# Block_GPIOs_USB2_0_I2S_SPI_GBe_and_CSI.net
KiCad netlist of a schematic drawn in Altium Designer
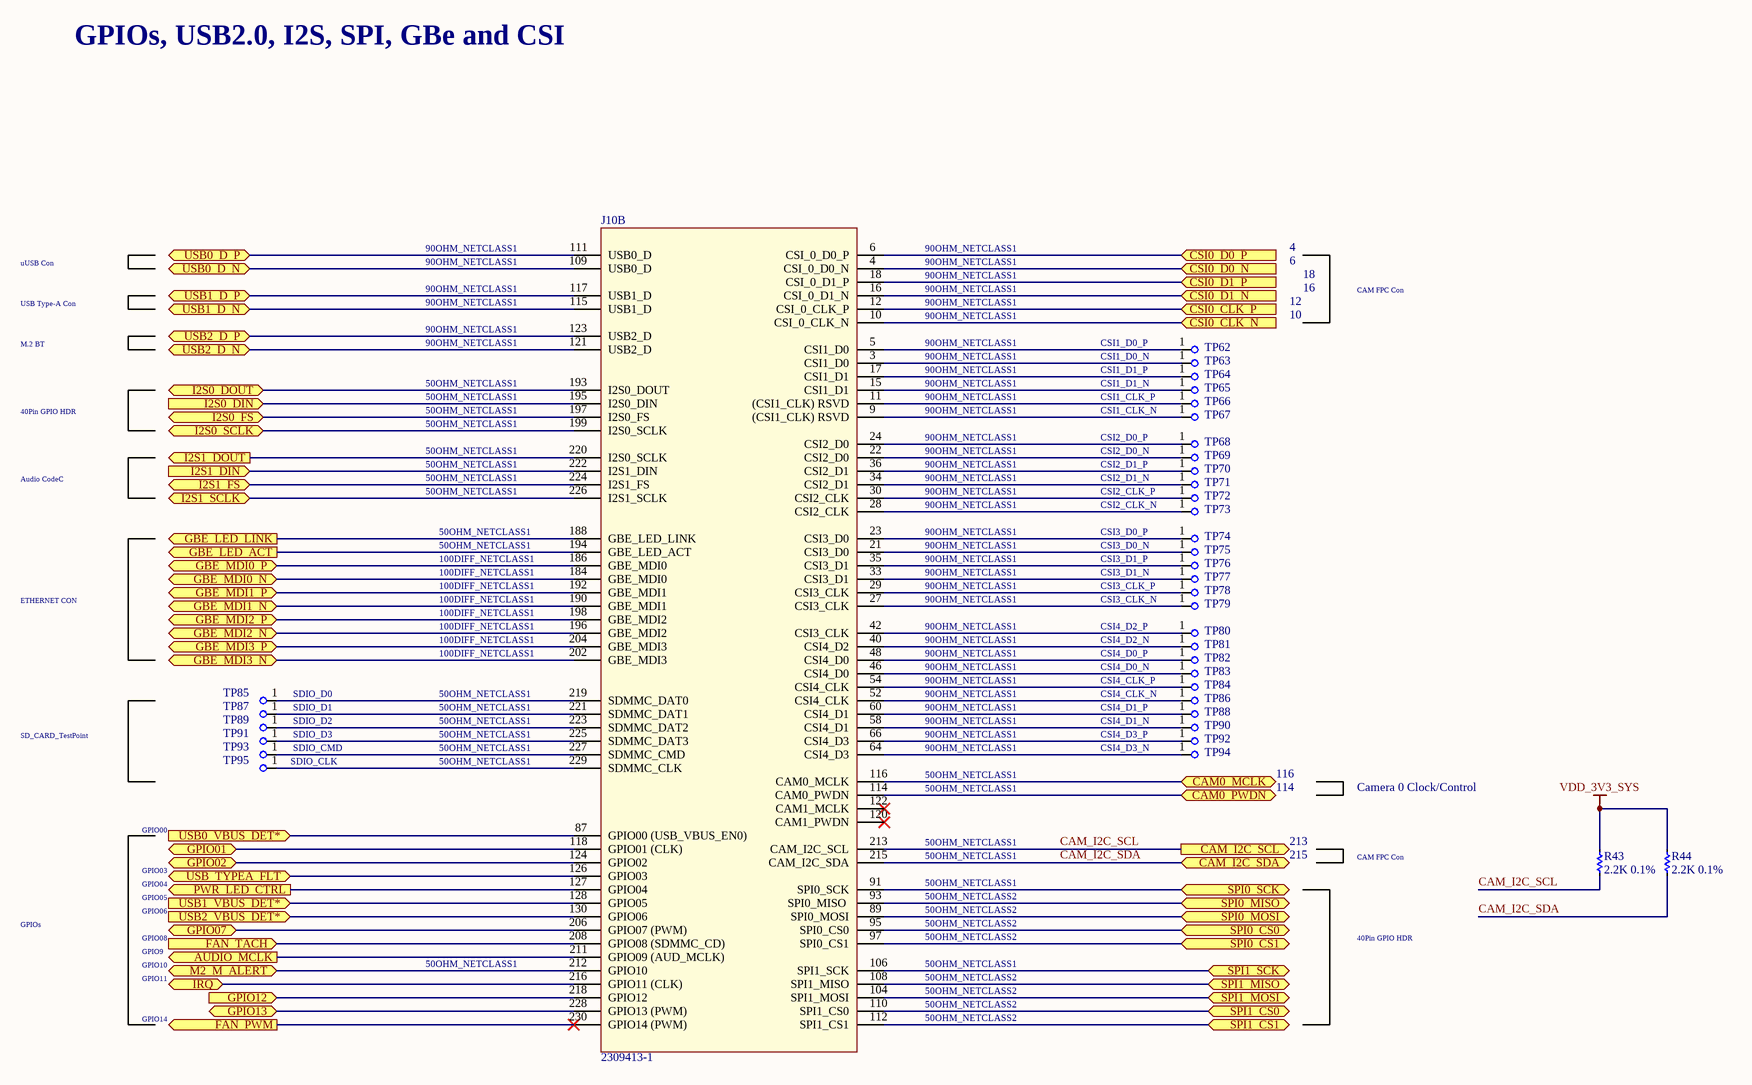
[diagram p0: Block_GPIOs, USB2.0, I2S, SPI, GBe and CSI.SchDoc]

(export (version "E")
  (design (tool "Eeschema 10.0.6"))
  (components
    (comp (ref "J10")
      (value "2309413-1")
      (footprint "2309413-1")
      (description "Conn DDR4 DIMM Socket SKT 260 POS 0.5mm Solder RA SMD T/R")
      (fields (field (name "MANUFACTURER") "TE Connectivity"))
      (libsource (lib "GM_Altium_Library") (part "2309413-1"))
    )
    (comp (ref "R43")
      (value "2.2K 0.1%")
      (footprint "R0603")
      (description "Res Thin Film 0603 2.2K Ohm 0.1% 1/16W ±25ppm/°C Molded SMD SMD Paper T/R")
      (fields
        (field (name "MANUFACTURER") "TE Connectivity Neohm")
        (field (name "MANUFACTURER PART NUMBER") "CPF0603B2K2E1")
      )
      (libsource (lib "GM_Altium_Library") (part "CPF0603B2K2E1"))
    )
    (comp (ref "R44")
      (value "2.2K 0.1%")
      (footprint "R0603")
      (description "Res Thin Film 0603 2.2K Ohm 0.1% 1/16W ±25ppm/°C Molded SMD SMD Paper T/R")
      (fields
        (field (name "MANUFACTURER") "TE Connectivity Neohm")
        (field (name "MANUFACTURER PART NUMBER") "CPF0603B2K2E1")
      )
      (libsource (lib "GM_Altium_Library") (part "CPF0603B2K2E1"))
    )
    (comp (ref "TP62")
      (value "CSI1_D0_P")
      (footprint "TestPoint_Pad_D1.0mm")
      (libsource (lib "GM_Altium_Library") (part "TestPoint_D1mm"))
    )
    (comp (ref "TP63")
      (value "CSI1_D0_N")
      (footprint "TestPoint_Pad_D1.0mm")
      (libsource (lib "GM_Altium_Library") (part "TestPoint_D1mm"))
    )
    (comp (ref "TP64")
      (value "CSI1_D1_P")
      (footprint "TestPoint_Pad_D1.0mm")
      (libsource (lib "GM_Altium_Library") (part "TestPoint_D1mm"))
    )
    (comp (ref "TP65")
      (value "CSI1_D1_N")
      (footprint "TestPoint_Pad_D1.0mm")
      (libsource (lib "GM_Altium_Library") (part "TestPoint_D1mm"))
    )
    (comp (ref "TP66")
      (value "CSI1_CLK_P")
      (footprint "TestPoint_Pad_D1.0mm")
      (libsource (lib "GM_Altium_Library") (part "TestPoint_D1mm"))
    )
    (comp (ref "TP67")
      (value "CSI1_CLK_N")
      (footprint "TestPoint_Pad_D1.0mm")
      (libsource (lib "GM_Altium_Library") (part "TestPoint_D1mm"))
    )
    (comp (ref "TP68")
      (value "CSI2_D0_P")
      (footprint "TestPoint_Pad_D1.0mm")
      (libsource (lib "GM_Altium_Library") (part "TestPoint_D1mm"))
    )
    (comp (ref "TP69")
      (value "CSI2_D0_N")
      (footprint "TestPoint_Pad_D1.0mm")
      (libsource (lib "GM_Altium_Library") (part "TestPoint_D1mm"))
    )
    (comp (ref "TP70")
      (value "CSI2_D1_P")
      (footprint "TestPoint_Pad_D1.0mm")
      (libsource (lib "GM_Altium_Library") (part "TestPoint_D1mm"))
    )
    (comp (ref "TP71")
      (value "CSI2_D1_N")
      (footprint "TestPoint_Pad_D1.0mm")
      (libsource (lib "GM_Altium_Library") (part "TestPoint_D1mm"))
    )
    (comp (ref "TP72")
      (value "CSI2_CLK_P")
      (footprint "TestPoint_Pad_D1.0mm")
      (libsource (lib "GM_Altium_Library") (part "TestPoint_D1mm"))
    )
    (comp (ref "TP73")
      (value "CSI2_CLK_N")
      (footprint "TestPoint_Pad_D1.0mm")
      (libsource (lib "GM_Altium_Library") (part "TestPoint_D1mm"))
    )
    (comp (ref "TP74")
      (value "CSI3_D0_P")
      (footprint "TestPoint_Pad_D1.0mm")
      (libsource (lib "GM_Altium_Library") (part "TestPoint_D1mm"))
    )
    (comp (ref "TP75")
      (value "CSI3_D0_N")
      (footprint "TestPoint_Pad_D1.0mm")
      (libsource (lib "GM_Altium_Library") (part "TestPoint_D1mm"))
    )
    (comp (ref "TP76")
      (value "CSI3_D1_P")
      (footprint "TestPoint_Pad_D1.0mm")
      (libsource (lib "GM_Altium_Library") (part "TestPoint_D1mm"))
    )
    (comp (ref "TP77")
      (value "CSI3_D1_N")
      (footprint "TestPoint_Pad_D1.0mm")
      (libsource (lib "GM_Altium_Library") (part "TestPoint_D1mm"))
    )
    (comp (ref "TP78")
      (value "CSI3_CLK_P")
      (footprint "TestPoint_Pad_D1.0mm")
      (libsource (lib "GM_Altium_Library") (part "TestPoint_D1mm"))
    )
    (comp (ref "TP79")
      (value "CSI3_CLK_N")
      (footprint "TestPoint_Pad_D1.0mm")
      (libsource (lib "GM_Altium_Library") (part "TestPoint_D1mm"))
    )
    (comp (ref "TP80")
      (value "CSI4_D2_P")
      (footprint "TestPoint_Pad_D1.0mm")
      (libsource (lib "GM_Altium_Library") (part "TestPoint_D1mm"))
    )
    (comp (ref "TP81")
      (value "CSI4_D2_N")
      (footprint "TestPoint_Pad_D1.0mm")
      (libsource (lib "GM_Altium_Library") (part "TestPoint_D1mm"))
    )
    (comp (ref "TP82")
      (value "CSI4_D0_P")
      (footprint "TestPoint_Pad_D1.0mm")
      (libsource (lib "GM_Altium_Library") (part "TestPoint_D1mm"))
    )
    (comp (ref "TP83")
      (value "CSI4_D0_N")
      (footprint "TestPoint_Pad_D1.0mm")
      (libsource (lib "GM_Altium_Library") (part "TestPoint_D1mm"))
    )
    (comp (ref "TP84")
      (value "CSI4_CLK_P")
      (footprint "TestPoint_Pad_D1.0mm")
      (libsource (lib "GM_Altium_Library") (part "TestPoint_D1mm"))
    )
    (comp (ref "TP85")
      (value "SDIO_D0")
      (footprint "TestPoint_Pad_D1.0mm")
      (libsource (lib "GM_Altium_Library") (part "TestPoint_D1mm"))
    )
    (comp (ref "TP86")
      (value "CSI4_CLK_N")
      (footprint "TestPoint_Pad_D1.0mm")
      (libsource (lib "GM_Altium_Library") (part "TestPoint_D1mm"))
    )
    (comp (ref "TP87")
      (value "SDIO_D1")
      (footprint "TestPoint_Pad_D1.0mm")
      (libsource (lib "GM_Altium_Library") (part "TestPoint_D1mm"))
    )
    (comp (ref "TP88")
      (value "CSI4_D1_P")
      (footprint "TestPoint_Pad_D1.0mm")
      (libsource (lib "GM_Altium_Library") (part "TestPoint_D1mm"))
    )
    (comp (ref "TP89")
      (value "SDIO_D2")
      (footprint "TestPoint_Pad_D1.0mm")
      (libsource (lib "GM_Altium_Library") (part "TestPoint_D1mm"))
    )
    (comp (ref "TP90")
      (value "CSI4_D1_N")
      (footprint "TestPoint_Pad_D1.0mm")
      (libsource (lib "GM_Altium_Library") (part "TestPoint_D1mm"))
    )
    (comp (ref "TP91")
      (value "SDIO_D3")
      (footprint "TestPoint_Pad_D1.0mm")
      (libsource (lib "GM_Altium_Library") (part "TestPoint_D1mm"))
    )
    (comp (ref "TP92")
      (value "CSI4_D3_P")
      (footprint "TestPoint_Pad_D1.0mm")
      (libsource (lib "GM_Altium_Library") (part "TestPoint_D1mm"))
    )
    (comp (ref "TP93")
      (value "SDIO_CMD")
      (footprint "TestPoint_Pad_D1.0mm")
      (libsource (lib "GM_Altium_Library") (part "TestPoint_D1mm"))
    )
    (comp (ref "TP94")
      (value "CSI4_D3_N")
      (footprint "TestPoint_Pad_D1.0mm")
      (libsource (lib "GM_Altium_Library") (part "TestPoint_D1mm"))
    )
    (comp (ref "TP95")
      (value "SDIO_CLK")
      (footprint "TestPoint_Pad_D1.0mm")
      (libsource (lib "GM_Altium_Library") (part "TestPoint_D1mm"))
    )
  )
  (nets
    (net (code "1") (name "/AUDIO_MCLK") (class "Default")
      (node (ref "J10") (pin "211") (pinfunction "GPIO09_(AUD_MCLK)_211") (pintype "passive"))
    )
    (net (code "2") (name "/CAM0_MCLK") (class "Default")
      (node (ref "J10") (pin "116") (pinfunction "CAM0_MCLK_116") (pintype "passive"))
    )
    (net (code "3") (name "/CAM0_PWDN") (class "Default")
      (node (ref "J10") (pin "114") (pinfunction "CAM0_PWDN_114") (pintype "passive"))
    )
    (net (code "4") (name "/CAM_I2C_SCL") (class "Default")
      (node (ref "J10") (pin "213") (pinfunction "CAM_I2C_SCL_213") (pintype "passive"))
      (node (ref "R43") (pin "1") (pinfunction "1_1") (pintype "passive"))
    )
    (net (code "5") (name "/CAM_I2C_SDA") (class "Default")
      (node (ref "J10") (pin "215") (pinfunction "CAM_I2C_SDA_215") (pintype "passive"))
      (node (ref "R44") (pin "1") (pinfunction "1_1") (pintype "passive"))
    )
    (net (code "6") (name "/CSI0_CLK_N") (class "Default")
      (node (ref "J10") (pin "10") (pinfunction "CSI_0_CLK_N_10") (pintype "passive"))
    )
    (net (code "7") (name "/CSI0_CLK_P") (class "Default")
      (node (ref "J10") (pin "12") (pinfunction "CSI_0_CLK_P_12") (pintype "passive"))
    )
    (net (code "8") (name "/CSI0_D0_N") (class "Default")
      (node (ref "J10") (pin "4") (pinfunction "CSI_0_D0_N_4") (pintype "passive"))
    )
    (net (code "9") (name "/CSI0_D0_P") (class "Default")
      (node (ref "J10") (pin "6") (pinfunction "CSI_0_D0_P_6") (pintype "passive"))
    )
    (net (code "10") (name "/CSI0_D1_N") (class "Default")
      (node (ref "J10") (pin "16") (pinfunction "CSI_0_D1_N_16") (pintype "passive"))
    )
    (net (code "11") (name "/CSI0_D1_P") (class "Default")
      (node (ref "J10") (pin "18") (pinfunction "CSI_0_D1_P_18") (pintype "passive"))
    )
    (net (code "12") (name "/FAN_PWM") (class "Default")
      (node (ref "J10") (pin "230") (pinfunction "GPIO14_(PWM)_230") (pintype "passive+no_connect"))
    )
    (net (code "13") (name "/FAN_TACH") (class "Default")
      (node (ref "J10") (pin "208") (pinfunction "GPIO08_(SDMMC_CD)_208") (pintype "passive"))
    )
    (net (code "14") (name "/GBE_LED_ACT") (class "Default")
      (node (ref "J10") (pin "194") (pinfunction "GBE_LED_ACT_194") (pintype "passive"))
    )
    (net (code "15") (name "/GBE_LED_LINK") (class "Default")
      (node (ref "J10") (pin "188") (pinfunction "GBE_LED_LINK_188") (pintype "passive"))
    )
    (net (code "16") (name "/GBE_MDI0_N") (class "Default")
      (node (ref "J10") (pin "184") (pinfunction "GBE_MDI0_184") (pintype "passive"))
    )
    (net (code "17") (name "/GBE_MDI0_P") (class "Default")
      (node (ref "J10") (pin "186") (pinfunction "GBE_MDI0_186") (pintype "passive"))
    )
    (net (code "18") (name "/GBE_MDI1_N") (class "Default")
      (node (ref "J10") (pin "190") (pinfunction "GBE_MDI1_190") (pintype "passive"))
    )
    (net (code "19") (name "/GBE_MDI1_P") (class "Default")
      (node (ref "J10") (pin "192") (pinfunction "GBE_MDI1_192") (pintype "passive"))
    )
    (net (code "20") (name "/GBE_MDI2_N") (class "Default")
      (node (ref "J10") (pin "196") (pinfunction "GBE_MDI2_196") (pintype "passive"))
    )
    (net (code "21") (name "/GBE_MDI2_P") (class "Default")
      (node (ref "J10") (pin "198") (pinfunction "GBE_MDI2_198") (pintype "passive"))
    )
    (net (code "22") (name "/GBE_MDI3_N") (class "Default")
      (node (ref "J10") (pin "202") (pinfunction "GBE_MDI3_202") (pintype "passive"))
    )
    (net (code "23") (name "/GBE_MDI3_P") (class "Default")
      (node (ref "J10") (pin "204") (pinfunction "GBE_MDI3_204") (pintype "passive"))
    )
    (net (code "24") (name "/GPIO01") (class "Default")
      (node (ref "J10") (pin "118") (pinfunction "GPIO01_(CLK)_118") (pintype "passive"))
    )
    (net (code "25") (name "/GPIO02") (class "Default")
      (node (ref "J10") (pin "124") (pinfunction "GPIO02_124") (pintype "passive"))
    )
    (net (code "26") (name "/GPIO07") (class "Default")
      (node (ref "J10") (pin "206") (pinfunction "GPIO07_(PWM)_206") (pintype "passive"))
    )
    (net (code "27") (name "/GPIO12") (class "Default")
      (node (ref "J10") (pin "218") (pinfunction "GPIO12_218") (pintype "passive"))
    )
    (net (code "28") (name "/GPIO13") (class "Default")
      (node (ref "J10") (pin "228") (pinfunction "GPIO13_(PWM)_228") (pintype "passive"))
    )
    (net (code "29") (name "/I2S0_DIN") (class "Default")
      (node (ref "J10") (pin "195") (pinfunction "I2S0_DIN_195") (pintype "passive"))
    )
    (net (code "30") (name "/I2S0_DOUT") (class "Default")
      (node (ref "J10") (pin "193") (pinfunction "I2S0_DOUT_193") (pintype "passive"))
    )
    (net (code "31") (name "/I2S0_FS") (class "Default")
      (node (ref "J10") (pin "197") (pinfunction "I2S0_FS_197") (pintype "passive"))
    )
    (net (code "32") (name "/I2S0_SCLK") (class "Default")
      (node (ref "J10") (pin "199") (pinfunction "I2S0_SCLK_199") (pintype "passive"))
    )
    (net (code "33") (name "/I2S1_DIN") (class "Default")
      (node (ref "J10") (pin "222") (pinfunction "I2S1_DIN_222") (pintype "passive"))
    )
    (net (code "34") (name "/I2S1_DOUT") (class "Default")
      (node (ref "J10") (pin "220") (pinfunction "I2S0_SCLK_220") (pintype "passive"))
    )
    (net (code "35") (name "/I2S1_FS") (class "Default")
      (node (ref "J10") (pin "224") (pinfunction "I2S1_FS_224") (pintype "passive"))
    )
    (net (code "36") (name "/I2S1_SCLK") (class "Default")
      (node (ref "J10") (pin "226") (pinfunction "I2S1_SCLK_226") (pintype "passive"))
    )
    (net (code "37") (name "/IRQ") (class "Default")
      (node (ref "J10") (pin "216") (pinfunction "GPIO11_(CLK)_216") (pintype "passive"))
    )
    (net (code "38") (name "/M2_M_ALERT") (class "Default")
      (node (ref "J10") (pin "212") (pinfunction "GPIO10_212") (pintype "passive"))
    )
    (net (code "39") (name "/PWR_LED_CTRL") (class "Default")
      (node (ref "J10") (pin "127") (pinfunction "GPIO04_127") (pintype "passive"))
    )
    (net (code "40") (name "/SPI0_CS0") (class "Default")
      (node (ref "J10") (pin "95") (pinfunction "SPI0_CS0_95") (pintype "passive"))
    )
    (net (code "41") (name "/SPI0_CS1") (class "Default")
      (node (ref "J10") (pin "97") (pinfunction "SPI0_CS1_97") (pintype "passive"))
    )
    (net (code "42") (name "/SPI0_MISO") (class "Default")
      (node (ref "J10") (pin "93") (pinfunction "SPI0_MISO_93") (pintype "passive"))
    )
    (net (code "43") (name "/SPI0_MOSI") (class "Default")
      (node (ref "J10") (pin "89") (pinfunction "SPI0_MOSI_89") (pintype "passive"))
    )
    (net (code "44") (name "/SPI0_SCK") (class "Default")
      (node (ref "J10") (pin "91") (pinfunction "SPI0_SCK_91") (pintype "passive"))
    )
    (net (code "45") (name "/SPI1_CS0") (class "Default")
      (node (ref "J10") (pin "110") (pinfunction "SPI1_CS0_110") (pintype "passive"))
    )
    (net (code "46") (name "/SPI1_CS1") (class "Default")
      (node (ref "J10") (pin "112") (pinfunction "SPI1_CS1_112") (pintype "passive"))
    )
    (net (code "47") (name "/SPI1_MISO") (class "Default")
      (node (ref "J10") (pin "108") (pinfunction "SPI1_MISO_108") (pintype "passive"))
    )
    (net (code "48") (name "/SPI1_MOSI") (class "Default")
      (node (ref "J10") (pin "104") (pinfunction "SPI1_MOSI_104") (pintype "passive"))
    )
    (net (code "49") (name "/SPI1_SCK") (class "Default")
      (node (ref "J10") (pin "106") (pinfunction "SPI1_SCK_106") (pintype "passive"))
    )
    (net (code "50") (name "/USB0_D_N") (class "Default")
      (node (ref "J10") (pin "109") (pinfunction "USB0_D_109") (pintype "passive"))
    )
    (net (code "51") (name "/USB0_D_P") (class "Default")
      (node (ref "J10") (pin "111") (pinfunction "USB0_D_111") (pintype "passive"))
    )
    (net (code "52") (name "/USB0_VBUS_DET*") (class "Default")
      (node (ref "J10") (pin "87") (pinfunction "GPIO00_(USB_VBUS_EN0)_87") (pintype "passive"))
    )
    (net (code "53") (name "/USB1_D_N") (class "Default")
      (node (ref "J10") (pin "115") (pinfunction "USB1_D_115") (pintype "passive"))
    )
    (net (code "54") (name "/USB1_D_P") (class "Default")
      (node (ref "J10") (pin "117") (pinfunction "USB1_D_117") (pintype "passive"))
    )
    (net (code "55") (name "/USB1_VBUS_DET*") (class "Default")
      (node (ref "J10") (pin "128") (pinfunction "GPIO05_128") (pintype "passive"))
    )
    (net (code "56") (name "/USB2_D_N") (class "Default")
      (node (ref "J10") (pin "121") (pinfunction "USB2_D_121") (pintype "passive"))
    )
    (net (code "57") (name "/USB2_D_P") (class "Default")
      (node (ref "J10") (pin "123") (pinfunction "USB2_D_123") (pintype "passive"))
    )
    (net (code "58") (name "/USB2_VBUS_DET*") (class "Default")
      (node (ref "J10") (pin "130") (pinfunction "GPIO06_130") (pintype "passive"))
    )
    (net (code "59") (name "/USB_TYPEA_FLT") (class "Default")
      (node (ref "J10") (pin "126") (pinfunction "GPIO03_126") (pintype "passive"))
    )
    (net (code "60") (name "Net-(J10B-(CSI1_CLK)_RSVD-Pad9)") (class "Default")
      (node (ref "J10") (pin "9") (pinfunction "(CSI1_CLK)_RSVD_9") (pintype "passive"))
      (node (ref "TP67") (pin "1") (pinfunction "1_1") (pintype "passive"))
    )
    (net (code "61") (name "Net-(J10B-(CSI1_CLK)_RSVD-Pad11)") (class "Default")
      (node (ref "J10") (pin "11") (pinfunction "(CSI1_CLK)_RSVD_11") (pintype "passive"))
      (node (ref "TP66") (pin "1") (pinfunction "1_1") (pintype "passive"))
    )
    (net (code "62") (name "Net-(J10B-CSI1_D0-Pad3)") (class "Default")
      (node (ref "J10") (pin "3") (pinfunction "CSI1_D0_3") (pintype "passive"))
      (node (ref "TP63") (pin "1") (pinfunction "1_1") (pintype "passive"))
    )
    (net (code "63") (name "Net-(J10B-CSI1_D0-Pad5)") (class "Default")
      (node (ref "J10") (pin "5") (pinfunction "CSI1_D0_5") (pintype "passive"))
      (node (ref "TP62") (pin "1") (pinfunction "1_1") (pintype "passive"))
    )
    (net (code "64") (name "Net-(J10B-CSI1_D1-Pad15)") (class "Default")
      (node (ref "J10") (pin "15") (pinfunction "CSI1_D1_15") (pintype "passive"))
      (node (ref "TP65") (pin "1") (pinfunction "1_1") (pintype "passive"))
    )
    (net (code "65") (name "Net-(J10B-CSI1_D1-Pad17)") (class "Default")
      (node (ref "J10") (pin "17") (pinfunction "CSI1_D1_17") (pintype "passive"))
      (node (ref "TP64") (pin "1") (pinfunction "1_1") (pintype "passive"))
    )
    (net (code "66") (name "Net-(J10B-CSI2_CLK-Pad28)") (class "Default")
      (node (ref "J10") (pin "28") (pinfunction "CSI2_CLK_28") (pintype "passive"))
      (node (ref "TP73") (pin "1") (pinfunction "1_1") (pintype "passive"))
    )
    (net (code "67") (name "Net-(J10B-CSI2_CLK-Pad30)") (class "Default")
      (node (ref "J10") (pin "30") (pinfunction "CSI2_CLK_30") (pintype "passive"))
      (node (ref "TP72") (pin "1") (pinfunction "1_1") (pintype "passive"))
    )
    (net (code "68") (name "Net-(J10B-CSI2_D0-Pad22)") (class "Default")
      (node (ref "J10") (pin "22") (pinfunction "CSI2_D0_22") (pintype "passive"))
      (node (ref "TP69") (pin "1") (pinfunction "1_1") (pintype "passive"))
    )
    (net (code "69") (name "Net-(J10B-CSI2_D0-Pad24)") (class "Default")
      (node (ref "J10") (pin "24") (pinfunction "CSI2_D0_24") (pintype "passive"))
      (node (ref "TP68") (pin "1") (pinfunction "1_1") (pintype "passive"))
    )
    (net (code "70") (name "Net-(J10B-CSI2_D1-Pad34)") (class "Default")
      (node (ref "J10") (pin "34") (pinfunction "CSI2_D1_34") (pintype "passive"))
      (node (ref "TP71") (pin "1") (pinfunction "1_1") (pintype "passive"))
    )
    (net (code "71") (name "Net-(J10B-CSI2_D1-Pad36)") (class "Default")
      (node (ref "J10") (pin "36") (pinfunction "CSI2_D1_36") (pintype "passive"))
      (node (ref "TP70") (pin "1") (pinfunction "1_1") (pintype "passive"))
    )
    (net (code "72") (name "Net-(J10B-CSI3_CLK-Pad27)") (class "Default")
      (node (ref "J10") (pin "27") (pinfunction "CSI3_CLK_27") (pintype "passive"))
      (node (ref "TP79") (pin "1") (pinfunction "1_1") (pintype "passive"))
    )
    (net (code "73") (name "Net-(J10B-CSI3_CLK-Pad29)") (class "Default")
      (node (ref "J10") (pin "29") (pinfunction "CSI3_CLK_29") (pintype "passive"))
      (node (ref "TP78") (pin "1") (pinfunction "1_1") (pintype "passive"))
    )
    (net (code "74") (name "Net-(J10B-CSI3_CLK-Pad42)") (class "Default")
      (node (ref "J10") (pin "42") (pinfunction "CSI3_CLK_42") (pintype "passive"))
      (node (ref "TP80") (pin "1") (pinfunction "1_1") (pintype "passive"))
    )
    (net (code "75") (name "Net-(J10B-CSI3_D0-Pad21)") (class "Default")
      (node (ref "J10") (pin "21") (pinfunction "CSI3_D0_21") (pintype "passive"))
      (node (ref "TP75") (pin "1") (pinfunction "1_1") (pintype "passive"))
    )
    (net (code "76") (name "Net-(J10B-CSI3_D0-Pad23)") (class "Default")
      (node (ref "J10") (pin "23") (pinfunction "CSI3_D0_23") (pintype "passive"))
      (node (ref "TP74") (pin "1") (pinfunction "1_1") (pintype "passive"))
    )
    (net (code "77") (name "Net-(J10B-CSI3_D1-Pad33)") (class "Default")
      (node (ref "J10") (pin "33") (pinfunction "CSI3_D1_33") (pintype "passive"))
      (node (ref "TP77") (pin "1") (pinfunction "1_1") (pintype "passive"))
    )
    (net (code "78") (name "Net-(J10B-CSI3_D1-Pad35)") (class "Default")
      (node (ref "J10") (pin "35") (pinfunction "CSI3_D1_35") (pintype "passive"))
      (node (ref "TP76") (pin "1") (pinfunction "1_1") (pintype "passive"))
    )
    (net (code "79") (name "Net-(J10B-CSI4_CLK-Pad52)") (class "Default")
      (node (ref "J10") (pin "52") (pinfunction "CSI4_CLK_52") (pintype "passive"))
      (node (ref "TP86") (pin "1") (pinfunction "1_1") (pintype "passive"))
    )
    (net (code "80") (name "Net-(J10B-CSI4_CLK-Pad54)") (class "Default")
      (node (ref "J10") (pin "54") (pinfunction "CSI4_CLK_54") (pintype "passive"))
      (node (ref "TP84") (pin "1") (pinfunction "1_1") (pintype "passive"))
    )
    (net (code "81") (name "Net-(J10B-CSI4_D0-Pad46)") (class "Default")
      (node (ref "J10") (pin "46") (pinfunction "CSI4_D0_46") (pintype "passive"))
      (node (ref "TP83") (pin "1") (pinfunction "1_1") (pintype "passive"))
    )
    (net (code "82") (name "Net-(J10B-CSI4_D0-Pad48)") (class "Default")
      (node (ref "J10") (pin "48") (pinfunction "CSI4_D0_48") (pintype "passive"))
      (node (ref "TP82") (pin "1") (pinfunction "1_1") (pintype "passive"))
    )
    (net (code "83") (name "Net-(J10B-CSI4_D1-Pad58)") (class "Default")
      (node (ref "J10") (pin "58") (pinfunction "CSI4_D1_58") (pintype "passive"))
      (node (ref "TP90") (pin "1") (pinfunction "1_1") (pintype "passive"))
    )
    (net (code "84") (name "Net-(J10B-CSI4_D1-Pad60)") (class "Default")
      (node (ref "J10") (pin "60") (pinfunction "CSI4_D1_60") (pintype "passive"))
      (node (ref "TP88") (pin "1") (pinfunction "1_1") (pintype "passive"))
    )
    (net (code "85") (name "Net-(J10B-CSI4_D2)") (class "Default")
      (node (ref "J10") (pin "40") (pinfunction "CSI4_D2_40") (pintype "passive"))
      (node (ref "TP81") (pin "1") (pinfunction "1_1") (pintype "passive"))
    )
    (net (code "86") (name "Net-(J10B-CSI4_D3-Pad64)") (class "Default")
      (node (ref "J10") (pin "64") (pinfunction "CSI4_D3_64") (pintype "passive"))
      (node (ref "TP94") (pin "1") (pinfunction "1_1") (pintype "passive"))
    )
    (net (code "87") (name "Net-(J10B-CSI4_D3-Pad66)") (class "Default")
      (node (ref "J10") (pin "66") (pinfunction "CSI4_D3_66") (pintype "passive"))
      (node (ref "TP92") (pin "1") (pinfunction "1_1") (pintype "passive"))
    )
    (net (code "88") (name "Net-(J10B-SDMMC_CLK)") (class "Default")
      (node (ref "J10") (pin "229") (pinfunction "SDMMC_CLK_229") (pintype "passive"))
      (node (ref "TP95") (pin "1") (pinfunction "1_1") (pintype "passive"))
    )
    (net (code "89") (name "Net-(J10B-SDMMC_CMD)") (class "Default")
      (node (ref "J10") (pin "227") (pinfunction "SDMMC_CMD_227") (pintype "passive"))
      (node (ref "TP93") (pin "1") (pinfunction "1_1") (pintype "passive"))
    )
    (net (code "90") (name "Net-(J10B-SDMMC_DAT0)") (class "Default")
      (node (ref "J10") (pin "219") (pinfunction "SDMMC_DAT0_219") (pintype "passive"))
      (node (ref "TP85") (pin "1") (pinfunction "1_1") (pintype "passive"))
    )
    (net (code "91") (name "Net-(J10B-SDMMC_DAT1)") (class "Default")
      (node (ref "J10") (pin "221") (pinfunction "SDMMC_DAT1_221") (pintype "passive"))
      (node (ref "TP87") (pin "1") (pinfunction "1_1") (pintype "passive"))
    )
    (net (code "92") (name "Net-(J10B-SDMMC_DAT2)") (class "Default")
      (node (ref "J10") (pin "223") (pinfunction "SDMMC_DAT2_223") (pintype "passive"))
      (node (ref "TP89") (pin "1") (pinfunction "1_1") (pintype "passive"))
    )
    (net (code "93") (name "Net-(J10B-SDMMC_DAT3)") (class "Default")
      (node (ref "J10") (pin "225") (pinfunction "SDMMC_DAT3_225") (pintype "passive"))
      (node (ref "TP91") (pin "1") (pinfunction "1_1") (pintype "passive"))
    )
    (net (code "94") (name "VDD_3V3_SYS") (class "Default")
      (node (ref "R43") (pin "2") (pinfunction "2_2") (pintype "passive"))
      (node (ref "R44") (pin "2") (pinfunction "2_2") (pintype "passive"))
    )
    (net (code "95") (name "unconnected-(J10B-CAM1_MCLK-Pad122)") (class "Default")
      (node (ref "J10") (pin "122") (pinfunction "CAM1_MCLK_122") (pintype "passive+no_connect"))
    )
    (net (code "96") (name "unconnected-(J10B-CAM1_PWDN-Pad120)") (class "Default")
      (node (ref "J10") (pin "120") (pinfunction "CAM1_PWDN_120") (pintype "passive+no_connect"))
    )
  )
)
